# Notch_schematic.net
KiCad netlist of a schematic drawn in Altium Designer
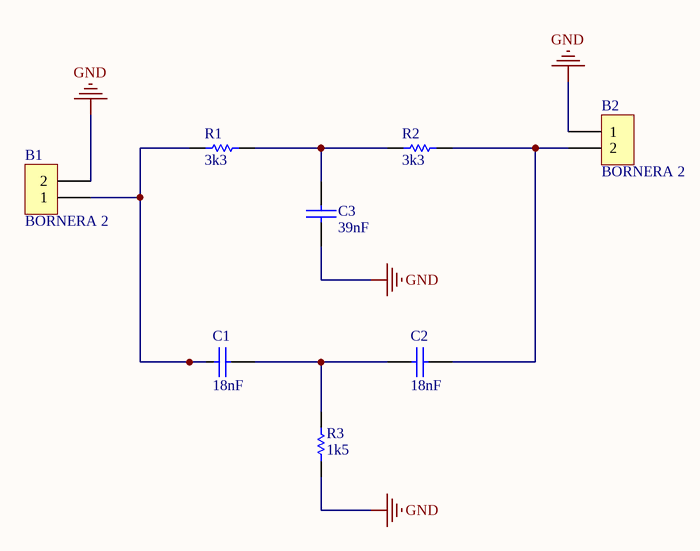
[diagram p0: Notch_schematic.SchDoc]

(export (version "E")
  (design (tool "Eeschema 10.0.6"))
  (components
    (comp (ref "B1") (value "BORNERA 2") (footprint "BORNERA2") (libsource (lib "") (part "BORNERA 2_1")))
    (comp (ref "B2")
      (value "BORNERA 2")
      (footprint "BORNERA2")
      (libsource (lib "LIBEBAL") (part "BORNERA 2"))
    )
    (comp (ref "C1") (value "18nF") (footprint "CAP200") (libsource (lib "LIBEBAL") (part "CAP")))
    (comp (ref "C2") (value "18nF") (footprint "CAP200") (libsource (lib "LIBEBAL") (part "CAP")))
    (comp (ref "C3") (value "39nF") (footprint "CAP200") (libsource (lib "LIBEBAL") (part "CAP")))
    (comp (ref "R1") (value "3k3") (footprint "RES400") (libsource (lib "LIBEBAL") (part "RES")))
    (comp (ref "R2") (value "3k3") (footprint "RES400") (libsource (lib "LIBEBAL") (part "RES")))
    (comp (ref "R3") (value "1k5") (footprint "RES400") (libsource (lib "LIBEBAL") (part "RES")))
  )
  (nets
    (net (code "1") (name "GND") (class "Default")
      (node (ref "B1") (pin "2") (pinfunction "2_2") (pintype "passive"))
      (node (ref "B2") (pin "1") (pinfunction "1_1") (pintype "passive"))
      (node (ref "C3") (pin "2") (pinfunction "2_2") (pintype "passive"))
      (node (ref "R3") (pin "1") (pinfunction "1_1") (pintype "passive"))
    )
    (net (code "2") (name "Net-(B1-Pad1)") (class "Default")
      (node (ref "B1") (pin "1") (pinfunction "1_1") (pintype "passive"))
      (node (ref "C1") (pin "1") (pinfunction "1_1") (pintype "passive"))
      (node (ref "R1") (pin "1") (pinfunction "1_1") (pintype "passive"))
    )
    (net (code "3") (name "Net-(B2-Pad2)") (class "Default")
      (node (ref "B2") (pin "2") (pinfunction "2_2") (pintype "passive"))
      (node (ref "C2") (pin "2") (pinfunction "2_2") (pintype "passive"))
      (node (ref "R2") (pin "2") (pinfunction "2_2") (pintype "passive"))
    )
    (net (code "4") (name "Net-(C1-Pad2)") (class "Default")
      (node (ref "C1") (pin "2") (pinfunction "2_2") (pintype "passive"))
      (node (ref "C2") (pin "1") (pinfunction "1_1") (pintype "passive"))
      (node (ref "R3") (pin "2") (pinfunction "2_2") (pintype "passive"))
    )
    (net (code "5") (name "Net-(C3-Pad1)") (class "Default")
      (node (ref "C3") (pin "1") (pinfunction "1_1") (pintype "passive"))
      (node (ref "R1") (pin "2") (pinfunction "2_2") (pintype "passive"))
      (node (ref "R2") (pin "1") (pinfunction "1_1") (pintype "passive"))
    )
  )
)
